# umodular_ctrl16.net
KiCad netlist of a schematic drawn in EAGLE
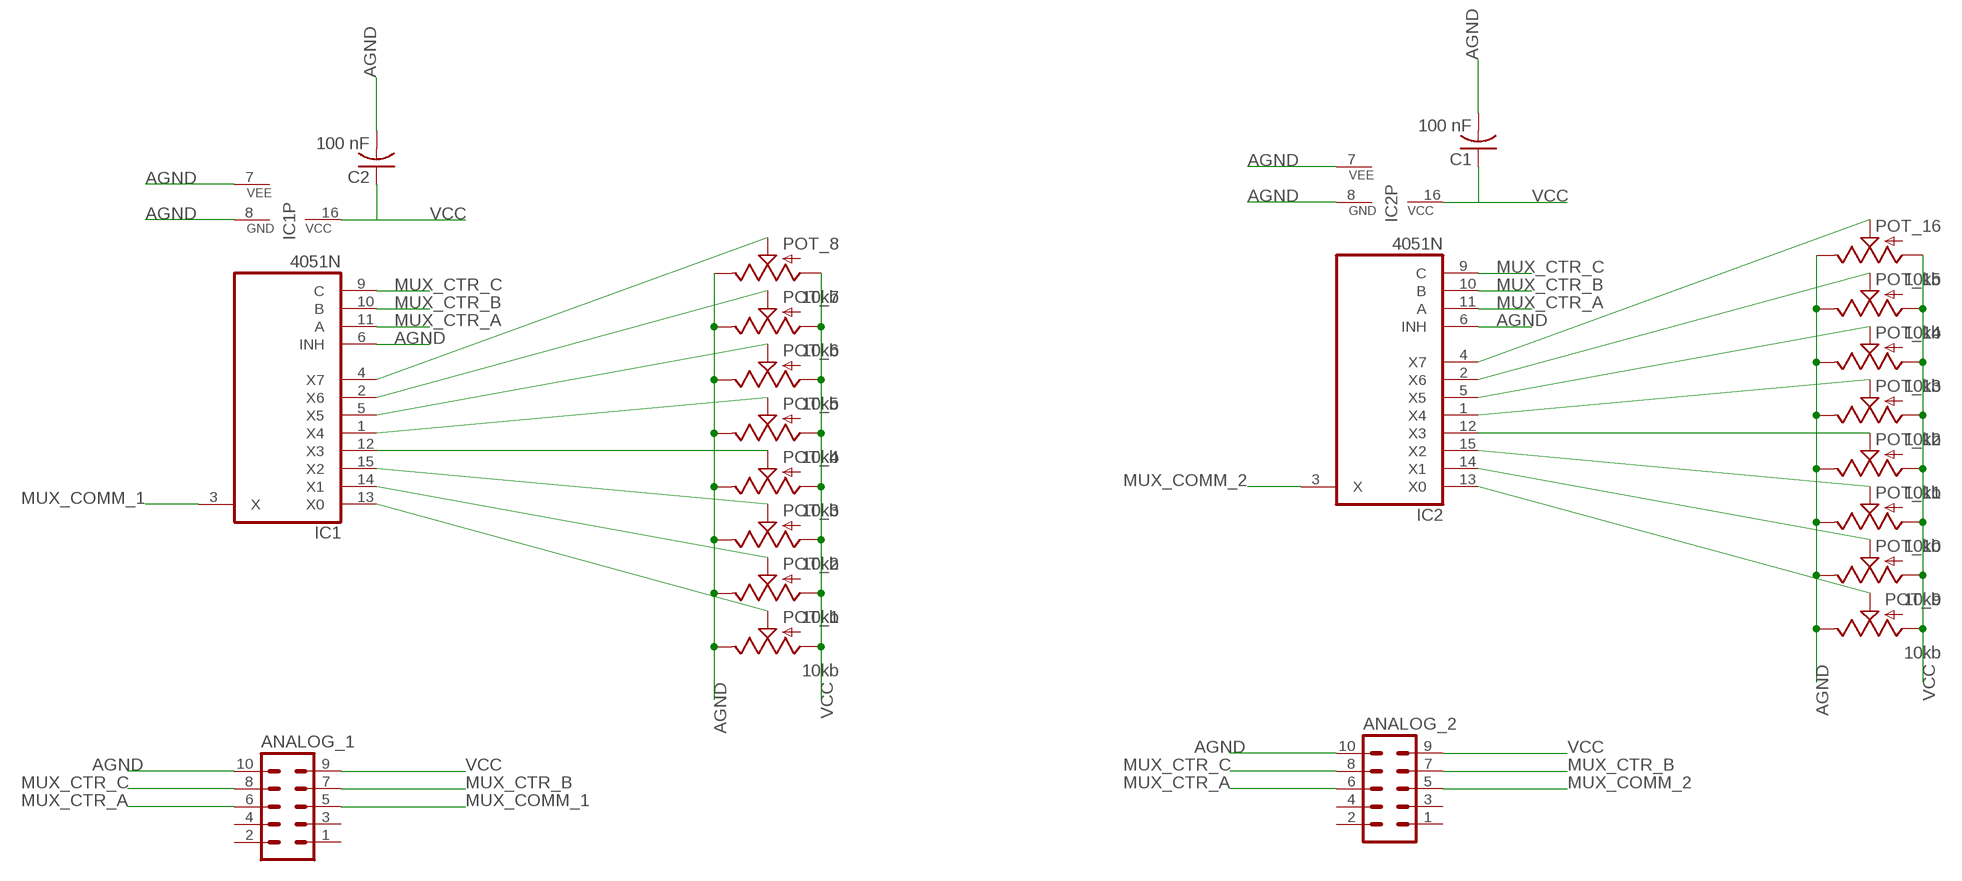
[diagram p0: schematic, sheet 1]
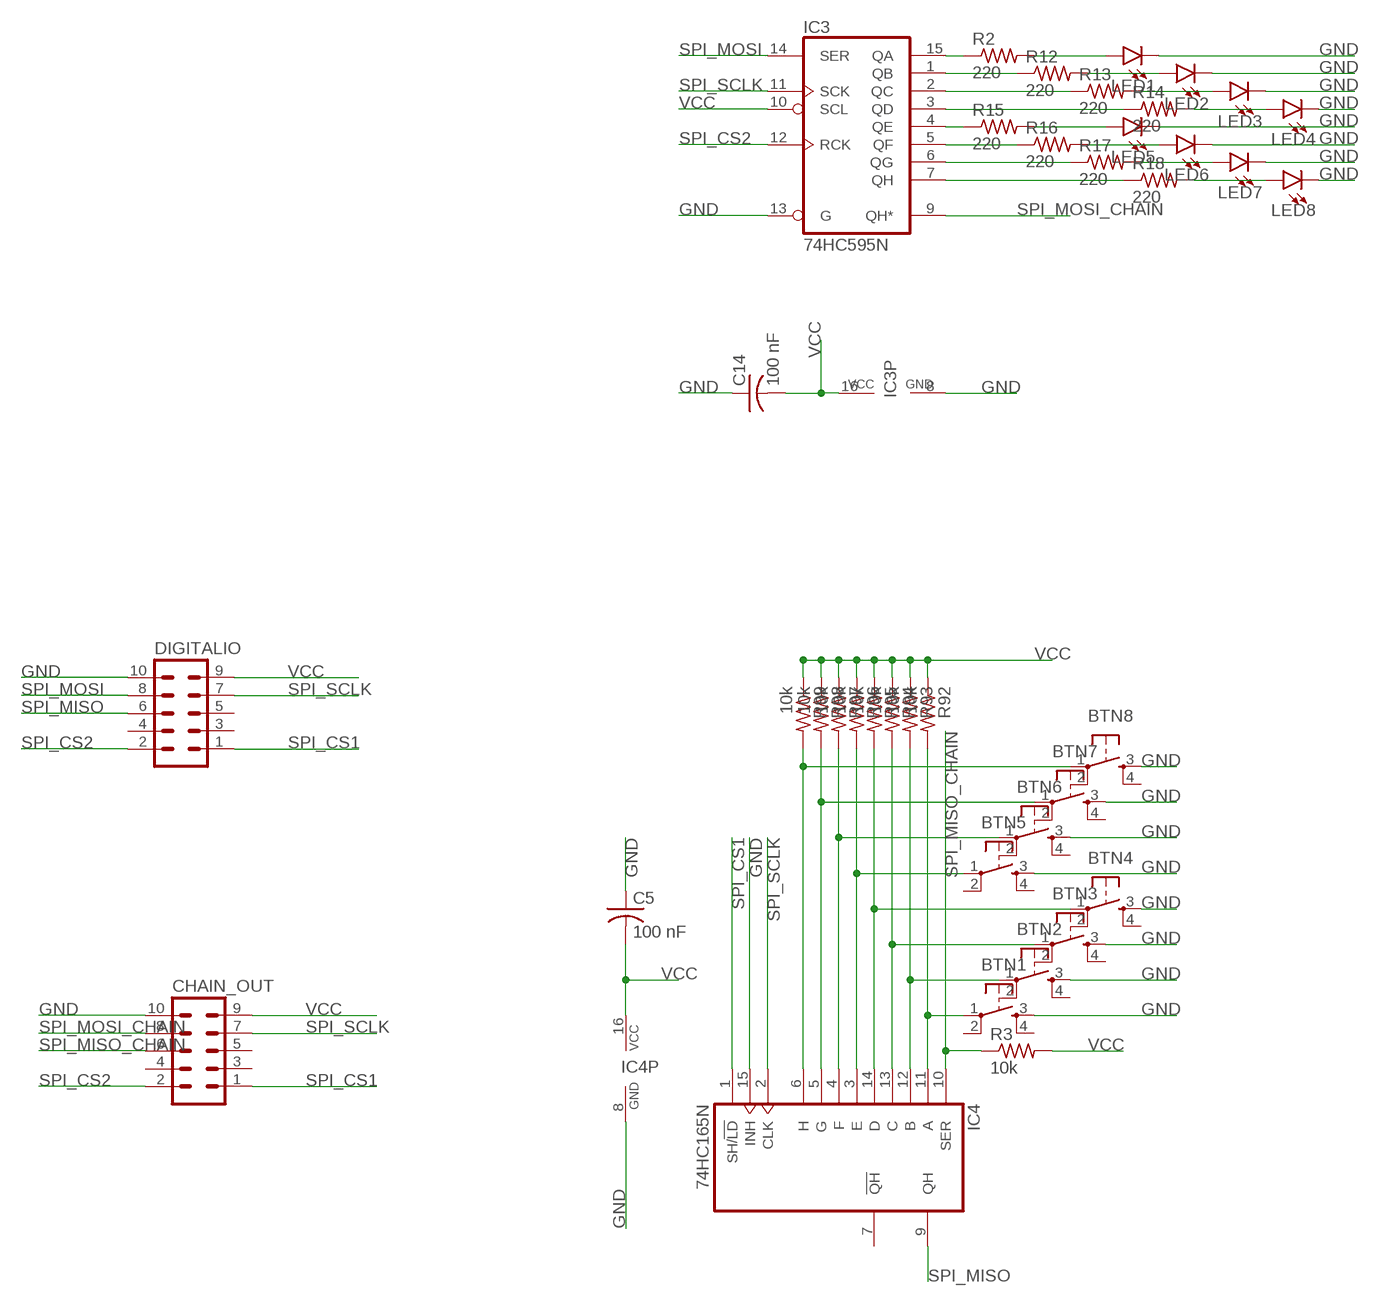
[diagram p1: schematic, sheet 2]

(export (version "E")
  (design (tool "Eeschema 10.0.6"))
  (components
    (comp (ref "ANALOG_1")
      (value "MA05-2")
      (footprint "eagle-import:MA05-2")
      (libsource (lib "eagle-import") (part "MA05-2"))
    )
    (comp (ref "ANALOG_2")
      (value "MA05-2")
      (footprint "eagle-import:MA05-2")
      (libsource (lib "eagle-import") (part "MA05-2"))
    )
    (comp (ref "C1")
      (value "100 nF")
      (footprint "eagle-import:C050-024X044")
      (libsource (lib "eagle-import") (part "C-US050-024X044"))
    )
    (comp (ref "C2")
      (value "100 nF")
      (footprint "eagle-import:C050-024X044")
      (libsource (lib "eagle-import") (part "C-US050-024X044"))
    )
    (comp (ref "IC1")
      (value "4051N")
      (footprint "eagle-import:DIL16")
      (libsource (lib "eagle-import") (part "4051N"))
    )
    (comp (ref "IC2")
      (value "4051N")
      (footprint "eagle-import:DIL16")
      (libsource (lib "eagle-import") (part "4051N"))
    )
    (comp (ref "POT_1")
      (value "10kb")
      (footprint "eagle-import:ALPS_POT")
      (libsource (lib "eagle-import") (part "POT"))
    )
    (comp (ref "POT_2")
      (value "10kb")
      (footprint "eagle-import:ALPS_POT")
      (libsource (lib "eagle-import") (part "POT"))
    )
    (comp (ref "POT_3")
      (value "10kb")
      (footprint "eagle-import:ALPS_POT")
      (libsource (lib "eagle-import") (part "POT"))
    )
    (comp (ref "POT_4")
      (value "10kb")
      (footprint "eagle-import:ALPS_POT")
      (libsource (lib "eagle-import") (part "POT"))
    )
    (comp (ref "POT_5")
      (value "10kb")
      (footprint "eagle-import:ALPS_POT")
      (libsource (lib "eagle-import") (part "POT"))
    )
    (comp (ref "POT_6")
      (value "10kb")
      (footprint "eagle-import:ALPS_POT")
      (libsource (lib "eagle-import") (part "POT"))
    )
    (comp (ref "POT_7")
      (value "10kb")
      (footprint "eagle-import:ALPS_POT")
      (libsource (lib "eagle-import") (part "POT"))
    )
    (comp (ref "POT_8")
      (value "10kb")
      (footprint "eagle-import:ALPS_POT")
      (libsource (lib "eagle-import") (part "POT"))
    )
    (comp (ref "POT_9")
      (value "10kb")
      (footprint "eagle-import:ALPS_POT")
      (libsource (lib "eagle-import") (part "POT"))
    )
    (comp (ref "POT_10")
      (value "10kb")
      (footprint "eagle-import:ALPS_POT")
      (libsource (lib "eagle-import") (part "POT"))
    )
    (comp (ref "POT_11")
      (value "10kb")
      (footprint "eagle-import:ALPS_POT")
      (libsource (lib "eagle-import") (part "POT"))
    )
    (comp (ref "POT_12")
      (value "10kb")
      (footprint "eagle-import:ALPS_POT")
      (libsource (lib "eagle-import") (part "POT"))
    )
    (comp (ref "POT_13")
      (value "10kb")
      (footprint "eagle-import:ALPS_POT")
      (libsource (lib "eagle-import") (part "POT"))
    )
    (comp (ref "POT_14")
      (value "10kb")
      (footprint "eagle-import:ALPS_POT")
      (libsource (lib "eagle-import") (part "POT"))
    )
    (comp (ref "POT_15")
      (value "10kb")
      (footprint "eagle-import:ALPS_POT")
      (libsource (lib "eagle-import") (part "POT"))
    )
    (comp (ref "POT_16")
      (value "10kb")
      (footprint "eagle-import:ALPS_POT")
      (libsource (lib "eagle-import") (part "POT"))
    )
    (comp (ref "BTN1")
      (value "TAC_SWITCHPTH")
      (footprint "eagle-import:TACTILE-PTH")
      (libsource (lib "eagle-import") (part "TAC_SWITCHPTH"))
    )
    (comp (ref "BTN2")
      (value "TAC_SWITCHPTH")
      (footprint "eagle-import:TACTILE-PTH")
      (libsource (lib "eagle-import") (part "TAC_SWITCHPTH"))
    )
    (comp (ref "BTN3")
      (value "TAC_SWITCHPTH")
      (footprint "eagle-import:TACTILE-PTH")
      (libsource (lib "eagle-import") (part "TAC_SWITCHPTH"))
    )
    (comp (ref "BTN4")
      (value "TAC_SWITCHPTH")
      (footprint "eagle-import:TACTILE-PTH")
      (libsource (lib "eagle-import") (part "TAC_SWITCHPTH"))
    )
    (comp (ref "BTN5")
      (value "TAC_SWITCHPTH")
      (footprint "eagle-import:TACTILE-PTH")
      (libsource (lib "eagle-import") (part "TAC_SWITCHPTH"))
    )
    (comp (ref "BTN6")
      (value "TAC_SWITCHPTH")
      (footprint "eagle-import:TACTILE-PTH")
      (libsource (lib "eagle-import") (part "TAC_SWITCHPTH"))
    )
    (comp (ref "BTN7")
      (value "TAC_SWITCHPTH")
      (footprint "eagle-import:TACTILE-PTH")
      (libsource (lib "eagle-import") (part "TAC_SWITCHPTH"))
    )
    (comp (ref "BTN8")
      (value "TAC_SWITCHPTH")
      (footprint "eagle-import:TACTILE-PTH")
      (libsource (lib "eagle-import") (part "TAC_SWITCHPTH"))
    )
    (comp (ref "C5")
      (value "100 nF")
      (footprint "eagle-import:C050-024X044")
      (libsource (lib "eagle-import") (part "C-US050-024X044"))
    )
    (comp (ref "C14")
      (value "100 nF")
      (footprint "eagle-import:C050-024X044")
      (libsource (lib "eagle-import") (part "C-US050-024X044"))
    )
    (comp (ref "CHAIN_OUT")
      (value "MA05-2")
      (footprint "eagle-import:MA05-2")
      (libsource (lib "eagle-import") (part "MA05-2"))
    )
    (comp (ref "DIGITALIO")
      (value "MA05-2")
      (footprint "eagle-import:MA05-2")
      (libsource (lib "eagle-import") (part "MA05-2"))
    )
    (comp (ref "IC3")
      (value "74HC595N")
      (footprint "eagle-import:DIL16")
      (libsource (lib "eagle-import") (part "74595NHC"))
    )
    (comp (ref "IC4")
      (value "74HC165N")
      (footprint "eagle-import:DIL16")
      (libsource (lib "eagle-import") (part "74165NHC"))
    )
    (comp (ref "LED1")
      (value "LED3MM")
      (footprint "eagle-import:LED_3MM")
      (libsource (lib "eagle-import") (part "LED3MM"))
    )
    (comp (ref "LED2")
      (value "LED3MM")
      (footprint "eagle-import:LED_3MM")
      (libsource (lib "eagle-import") (part "LED3MM"))
    )
    (comp (ref "LED3")
      (value "LED3MM")
      (footprint "eagle-import:LED_3MM")
      (libsource (lib "eagle-import") (part "LED3MM"))
    )
    (comp (ref "LED4")
      (value "LED3MM")
      (footprint "eagle-import:LED_3MM")
      (libsource (lib "eagle-import") (part "LED3MM"))
    )
    (comp (ref "LED5")
      (value "LED3MM")
      (footprint "eagle-import:LED_3MM")
      (libsource (lib "eagle-import") (part "LED3MM"))
    )
    (comp (ref "LED6")
      (value "LED3MM")
      (footprint "eagle-import:LED_3MM")
      (libsource (lib "eagle-import") (part "LED3MM"))
    )
    (comp (ref "LED7")
      (value "LED3MM")
      (footprint "eagle-import:LED_3MM")
      (libsource (lib "eagle-import") (part "LED3MM"))
    )
    (comp (ref "LED8")
      (value "LED3MM")
      (footprint "eagle-import:LED_3MM")
      (libsource (lib "eagle-import") (part "LED3MM"))
    )
    (comp (ref "R2")
      (value "220")
      (footprint "eagle-import:0204_7")
      (libsource (lib "eagle-import") (part "R-US_0204/7"))
    )
    (comp (ref "R3")
      (value "10k")
      (footprint "eagle-import:0204_7")
      (libsource (lib "eagle-import") (part "resistor_R-US_0204/7"))
    )
    (comp (ref "R12")
      (value "220")
      (footprint "eagle-import:0204_7")
      (libsource (lib "eagle-import") (part "R-US_0204/7"))
    )
    (comp (ref "R13")
      (value "220")
      (footprint "eagle-import:0204_7")
      (libsource (lib "eagle-import") (part "R-US_0204/7"))
    )
    (comp (ref "R14")
      (value "220")
      (footprint "eagle-import:0204_7")
      (libsource (lib "eagle-import") (part "R-US_0204/7"))
    )
    (comp (ref "R15")
      (value "220")
      (footprint "eagle-import:0204_7")
      (libsource (lib "eagle-import") (part "R-US_0204/7"))
    )
    (comp (ref "R16")
      (value "220")
      (footprint "eagle-import:0204_7")
      (libsource (lib "eagle-import") (part "R-US_0204/7"))
    )
    (comp (ref "R17")
      (value "220")
      (footprint "eagle-import:0204_7")
      (libsource (lib "eagle-import") (part "R-US_0204/7"))
    )
    (comp (ref "R18")
      (value "220")
      (footprint "eagle-import:0204_7")
      (libsource (lib "eagle-import") (part "R-US_0204/7"))
    )
    (comp (ref "R92")
      (value "10k")
      (footprint "eagle-import:0204_7")
      (libsource (lib "eagle-import") (part "resistor_R-US_0204/7"))
    )
    (comp (ref "R93")
      (value "10k")
      (footprint "eagle-import:0204_7")
      (libsource (lib "eagle-import") (part "resistor_R-US_0204/7"))
    )
    (comp (ref "R94")
      (value "10k")
      (footprint "eagle-import:0204_7")
      (libsource (lib "eagle-import") (part "resistor_R-US_0204/7"))
    )
    (comp (ref "R95")
      (value "10k")
      (footprint "eagle-import:0204_7")
      (libsource (lib "eagle-import") (part "resistor_R-US_0204/7"))
    )
    (comp (ref "R96")
      (value "10k")
      (footprint "eagle-import:0204_7")
      (libsource (lib "eagle-import") (part "resistor_R-US_0204/7"))
    )
    (comp (ref "R97")
      (value "10k")
      (footprint "eagle-import:0204_7")
      (libsource (lib "eagle-import") (part "resistor_R-US_0204/7"))
    )
    (comp (ref "R98")
      (value "10k")
      (footprint "eagle-import:0204_7")
      (libsource (lib "eagle-import") (part "resistor_R-US_0204/7"))
    )
    (comp (ref "R99")
      (value "10k")
      (footprint "eagle-import:0204_7")
      (libsource (lib "eagle-import") (part "resistor_R-US_0204/7"))
    )
  )
  (nets
    (net (code "1") (name "AGND") (class "Default")
      (node (ref "ANALOG_1") (pin "10") (pinfunction "10_10") (pintype "passive"))
      (node (ref "ANALOG_2") (pin "10") (pinfunction "10_10") (pintype "passive"))
      (node (ref "C1") (pin "2") (pinfunction "2_2") (pintype "passive"))
      (node (ref "C2") (pin "2") (pinfunction "2_2") (pintype "passive"))
      (node (ref "IC1") (pin "6") (pinfunction "INH_6") (pintype "input"))
      (node (ref "IC1") (pin "7") (pinfunction "VEE_7") (pintype "power_in"))
      (node (ref "IC1") (pin "8") (pinfunction "GND_8") (pintype "power_in"))
      (node (ref "IC2") (pin "6") (pinfunction "INH_6") (pintype "input"))
      (node (ref "IC2") (pin "7") (pinfunction "VEE_7") (pintype "power_in"))
      (node (ref "IC2") (pin "8") (pinfunction "GND_8") (pintype "power_in"))
      (node (ref "POT_1") (pin "P$1") (pinfunction "E_P$1") (pintype "passive"))
      (node (ref "POT_10") (pin "P$1") (pinfunction "E_P$1") (pintype "passive"))
      (node (ref "POT_11") (pin "P$1") (pinfunction "E_P$1") (pintype "passive"))
      (node (ref "POT_12") (pin "P$1") (pinfunction "E_P$1") (pintype "passive"))
      (node (ref "POT_13") (pin "P$1") (pinfunction "E_P$1") (pintype "passive"))
      (node (ref "POT_14") (pin "P$1") (pinfunction "E_P$1") (pintype "passive"))
      (node (ref "POT_15") (pin "P$1") (pinfunction "E_P$1") (pintype "passive"))
      (node (ref "POT_16") (pin "P$1") (pinfunction "E_P$1") (pintype "passive"))
      (node (ref "POT_2") (pin "P$1") (pinfunction "E_P$1") (pintype "passive"))
      (node (ref "POT_3") (pin "P$1") (pinfunction "E_P$1") (pintype "passive"))
      (node (ref "POT_4") (pin "P$1") (pinfunction "E_P$1") (pintype "passive"))
      (node (ref "POT_5") (pin "P$1") (pinfunction "E_P$1") (pintype "passive"))
      (node (ref "POT_6") (pin "P$1") (pinfunction "E_P$1") (pintype "passive"))
      (node (ref "POT_7") (pin "P$1") (pinfunction "E_P$1") (pintype "passive"))
      (node (ref "POT_8") (pin "P$1") (pinfunction "E_P$1") (pintype "passive"))
      (node (ref "POT_9") (pin "P$1") (pinfunction "E_P$1") (pintype "passive"))
    )
    (net (code "2") (name "GND") (class "Default")
      (node (ref "BTN1") (pin "3") (pinfunction "3_3") (pintype "passive"))
      (node (ref "BTN2") (pin "3") (pinfunction "3_3") (pintype "passive"))
      (node (ref "BTN3") (pin "3") (pinfunction "3_3") (pintype "passive"))
      (node (ref "BTN4") (pin "3") (pinfunction "3_3") (pintype "passive"))
      (node (ref "BTN5") (pin "3") (pinfunction "3_3") (pintype "passive"))
      (node (ref "BTN6") (pin "3") (pinfunction "3_3") (pintype "passive"))
      (node (ref "BTN7") (pin "3") (pinfunction "3_3") (pintype "passive"))
      (node (ref "BTN8") (pin "3") (pinfunction "3_3") (pintype "passive"))
      (node (ref "C14") (pin "1") (pinfunction "1_1") (pintype "passive"))
      (node (ref "C5") (pin "1") (pinfunction "1_1") (pintype "passive"))
      (node (ref "CHAIN_OUT") (pin "10") (pinfunction "10_10") (pintype "passive"))
      (node (ref "DIGITALIO") (pin "10") (pinfunction "10_10") (pintype "passive"))
      (node (ref "IC3") (pin "13") (pinfunction "G_13") (pintype "input"))
      (node (ref "IC3") (pin "8") (pinfunction "GND_8") (pintype "power_in"))
      (node (ref "IC4") (pin "15") (pinfunction "INH_15") (pintype "input"))
      (node (ref "IC4") (pin "8") (pinfunction "GND_8") (pintype "power_in"))
      (node (ref "LED1") (pin "K") (pinfunction "C_K") (pintype "passive"))
      (node (ref "LED2") (pin "K") (pinfunction "C_K") (pintype "passive"))
      (node (ref "LED3") (pin "K") (pinfunction "C_K") (pintype "passive"))
      (node (ref "LED4") (pin "K") (pinfunction "C_K") (pintype "passive"))
      (node (ref "LED5") (pin "K") (pinfunction "C_K") (pintype "passive"))
      (node (ref "LED6") (pin "K") (pinfunction "C_K") (pintype "passive"))
      (node (ref "LED7") (pin "K") (pinfunction "C_K") (pintype "passive"))
      (node (ref "LED8") (pin "K") (pinfunction "C_K") (pintype "passive"))
    )
    (net (code "3") (name "MUX_COMM_1") (class "Default")
      (node (ref "ANALOG_1") (pin "5") (pinfunction "5_5") (pintype "passive"))
      (node (ref "IC1") (pin "3") (pinfunction "X_3") (pintype "bidirectional"))
    )
    (net (code "4") (name "MUX_COMM_2") (class "Default")
      (node (ref "ANALOG_2") (pin "5") (pinfunction "5_5") (pintype "passive"))
      (node (ref "IC2") (pin "3") (pinfunction "X_3") (pintype "bidirectional"))
    )
    (net (code "5") (name "MUX_CTR_A") (class "Default")
      (node (ref "ANALOG_1") (pin "6") (pinfunction "6_6") (pintype "passive"))
      (node (ref "ANALOG_2") (pin "6") (pinfunction "6_6") (pintype "passive"))
      (node (ref "IC1") (pin "11") (pinfunction "A_11") (pintype "input"))
      (node (ref "IC2") (pin "11") (pinfunction "A_11") (pintype "input"))
    )
    (net (code "6") (name "MUX_CTR_B") (class "Default")
      (node (ref "ANALOG_1") (pin "7") (pinfunction "7_7") (pintype "passive"))
      (node (ref "ANALOG_2") (pin "7") (pinfunction "7_7") (pintype "passive"))
      (node (ref "IC1") (pin "10") (pinfunction "B_10") (pintype "input"))
      (node (ref "IC2") (pin "10") (pinfunction "B_10") (pintype "input"))
    )
    (net (code "7") (name "MUX_CTR_C") (class "Default")
      (node (ref "ANALOG_1") (pin "8") (pinfunction "8_8") (pintype "passive"))
      (node (ref "ANALOG_2") (pin "8") (pinfunction "8_8") (pintype "passive"))
      (node (ref "IC1") (pin "9") (pinfunction "C_9") (pintype "input"))
      (node (ref "IC2") (pin "9") (pinfunction "C_9") (pintype "input"))
    )
    (net (code "8") (name "Net-(IC1A-X0)") (class "Default")
      (node (ref "IC1") (pin "13") (pinfunction "X0_13") (pintype "bidirectional"))
      (node (ref "POT_1") (pin "P$2") (pinfunction "S_P$2") (pintype "passive"))
    )
    (net (code "9") (name "Net-(IC1A-X1)") (class "Default")
      (node (ref "IC1") (pin "14") (pinfunction "X1_14") (pintype "bidirectional"))
      (node (ref "POT_2") (pin "P$2") (pinfunction "S_P$2") (pintype "passive"))
    )
    (net (code "10") (name "Net-(IC1A-X2)") (class "Default")
      (node (ref "IC1") (pin "15") (pinfunction "X2_15") (pintype "bidirectional"))
      (node (ref "POT_3") (pin "P$2") (pinfunction "S_P$2") (pintype "passive"))
    )
    (net (code "11") (name "Net-(IC1A-X3)") (class "Default")
      (node (ref "IC1") (pin "12") (pinfunction "X3_12") (pintype "bidirectional"))
      (node (ref "POT_4") (pin "P$2") (pinfunction "S_P$2") (pintype "passive"))
    )
    (net (code "12") (name "Net-(IC1A-X4)") (class "Default")
      (node (ref "IC1") (pin "1") (pinfunction "X4_1") (pintype "bidirectional"))
      (node (ref "POT_5") (pin "P$2") (pinfunction "S_P$2") (pintype "passive"))
    )
    (net (code "13") (name "Net-(IC1A-X5)") (class "Default")
      (node (ref "IC1") (pin "5") (pinfunction "X5_5") (pintype "bidirectional"))
      (node (ref "POT_6") (pin "P$2") (pinfunction "S_P$2") (pintype "passive"))
    )
    (net (code "14") (name "Net-(IC1A-X6)") (class "Default")
      (node (ref "IC1") (pin "2") (pinfunction "X6_2") (pintype "bidirectional"))
      (node (ref "POT_7") (pin "P$2") (pinfunction "S_P$2") (pintype "passive"))
    )
    (net (code "15") (name "Net-(IC1A-X7)") (class "Default")
      (node (ref "IC1") (pin "4") (pinfunction "X7_4") (pintype "bidirectional"))
      (node (ref "POT_8") (pin "P$2") (pinfunction "S_P$2") (pintype "passive"))
    )
    (net (code "16") (name "Net-(IC2A-X0)") (class "Default")
      (node (ref "IC2") (pin "13") (pinfunction "X0_13") (pintype "bidirectional"))
      (node (ref "POT_9") (pin "P$2") (pinfunction "S_P$2") (pintype "passive"))
    )
    (net (code "17") (name "Net-(IC2A-X1)") (class "Default")
      (node (ref "IC2") (pin "14") (pinfunction "X1_14") (pintype "bidirectional"))
      (node (ref "POT_10") (pin "P$2") (pinfunction "S_P$2") (pintype "passive"))
    )
    (net (code "18") (name "Net-(IC2A-X2)") (class "Default")
      (node (ref "IC2") (pin "15") (pinfunction "X2_15") (pintype "bidirectional"))
      (node (ref "POT_11") (pin "P$2") (pinfunction "S_P$2") (pintype "passive"))
    )
    (net (code "19") (name "Net-(IC2A-X3)") (class "Default")
      (node (ref "IC2") (pin "12") (pinfunction "X3_12") (pintype "bidirectional"))
      (node (ref "POT_12") (pin "P$2") (pinfunction "S_P$2") (pintype "passive"))
    )
    (net (code "20") (name "Net-(IC2A-X4)") (class "Default")
      (node (ref "IC2") (pin "1") (pinfunction "X4_1") (pintype "bidirectional"))
      (node (ref "POT_13") (pin "P$2") (pinfunction "S_P$2") (pintype "passive"))
    )
    (net (code "21") (name "Net-(IC2A-X5)") (class "Default")
      (node (ref "IC2") (pin "5") (pinfunction "X5_5") (pintype "bidirectional"))
      (node (ref "POT_14") (pin "P$2") (pinfunction "S_P$2") (pintype "passive"))
    )
    (net (code "22") (name "Net-(IC2A-X6)") (class "Default")
      (node (ref "IC2") (pin "2") (pinfunction "X6_2") (pintype "bidirectional"))
      (node (ref "POT_15") (pin "P$2") (pinfunction "S_P$2") (pintype "passive"))
    )
    (net (code "23") (name "Net-(IC2A-X7)") (class "Default")
      (node (ref "IC2") (pin "4") (pinfunction "X7_4") (pintype "bidirectional"))
      (node (ref "POT_16") (pin "P$2") (pinfunction "S_P$2") (pintype "passive"))
    )
    (net (code "24") (name "Net-(IC3A-QA)") (class "Default")
      (node (ref "IC3") (pin "15") (pinfunction "QA_15") (pintype "tri_state"))
      (node (ref "R2") (pin "1") (pinfunction "1_1") (pintype "passive"))
    )
    (net (code "25") (name "Net-(IC3A-QB)") (class "Default")
      (node (ref "IC3") (pin "1") (pinfunction "QB_1") (pintype "tri_state"))
      (node (ref "R12") (pin "1") (pinfunction "1_1") (pintype "passive"))
    )
    (net (code "26") (name "Net-(IC3A-QC)") (class "Default")
      (node (ref "IC3") (pin "2") (pinfunction "QC_2") (pintype "tri_state"))
      (node (ref "R13") (pin "1") (pinfunction "1_1") (pintype "passive"))
    )
    (net (code "27") (name "Net-(IC3A-QD)") (class "Default")
      (node (ref "IC3") (pin "3") (pinfunction "QD_3") (pintype "tri_state"))
      (node (ref "R14") (pin "1") (pinfunction "1_1") (pintype "passive"))
    )
    (net (code "28") (name "Net-(IC3A-QE)") (class "Default")
      (node (ref "IC3") (pin "4") (pinfunction "QE_4") (pintype "tri_state"))
      (node (ref "R15") (pin "1") (pinfunction "1_1") (pintype "passive"))
    )
    (net (code "29") (name "Net-(IC3A-QF)") (class "Default")
      (node (ref "IC3") (pin "5") (pinfunction "QF_5") (pintype "tri_state"))
      (node (ref "R16") (pin "1") (pinfunction "1_1") (pintype "passive"))
    )
    (net (code "30") (name "Net-(IC3A-QG)") (class "Default")
      (node (ref "IC3") (pin "6") (pinfunction "QG_6") (pintype "tri_state"))
      (node (ref "R17") (pin "1") (pinfunction "1_1") (pintype "passive"))
    )
    (net (code "31") (name "Net-(IC3A-QH)") (class "Default")
      (node (ref "IC3") (pin "7") (pinfunction "QH_7") (pintype "tri_state"))
      (node (ref "R18") (pin "1") (pinfunction "1_1") (pintype "passive"))
    )
    (net (code "32") (name "Net-(IC4A-A)") (class "Default")
      (node (ref "BTN1") (pin "1") (pinfunction "1_1") (pintype "passive"))
      (node (ref "IC4") (pin "11") (pinfunction "A_11") (pintype "input"))
      (node (ref "R92") (pin "2") (pinfunction "2_2") (pintype "passive"))
    )
    (net (code "33") (name "Net-(IC4A-B)") (class "Default")
      (node (ref "BTN2") (pin "1") (pinfunction "1_1") (pintype "passive"))
      (node (ref "IC4") (pin "12") (pinfunction "B_12") (pintype "input"))
      (node (ref "R93") (pin "2") (pinfunction "2_2") (pintype "passive"))
    )
    (net (code "34") (name "Net-(IC4A-C)") (class "Default")
      (node (ref "BTN3") (pin "1") (pinfunction "1_1") (pintype "passive"))
      (node (ref "IC4") (pin "13") (pinfunction "C_13") (pintype "input"))
      (node (ref "R94") (pin "2") (pinfunction "2_2") (pintype "passive"))
    )
    (net (code "35") (name "Net-(IC4A-D)") (class "Default")
      (node (ref "BTN4") (pin "1") (pinfunction "1_1") (pintype "passive"))
      (node (ref "IC4") (pin "14") (pinfunction "D_14") (pintype "input"))
      (node (ref "R95") (pin "2") (pinfunction "2_2") (pintype "passive"))
    )
    (net (code "36") (name "Net-(IC4A-E)") (class "Default")
      (node (ref "BTN5") (pin "1") (pinfunction "1_1") (pintype "passive"))
      (node (ref "IC4") (pin "3") (pinfunction "E_3") (pintype "input"))
      (node (ref "R96") (pin "2") (pinfunction "2_2") (pintype "passive"))
    )
    (net (code "37") (name "Net-(IC4A-F)") (class "Default")
      (node (ref "BTN6") (pin "1") (pinfunction "1_1") (pintype "passive"))
      (node (ref "IC4") (pin "4") (pinfunction "F_4") (pintype "input"))
      (node (ref "R97") (pin "2") (pinfunction "2_2") (pintype "passive"))
    )
    (net (code "38") (name "Net-(IC4A-G)") (class "Default")
      (node (ref "BTN7") (pin "1") (pinfunction "1_1") (pintype "passive"))
      (node (ref "IC4") (pin "5") (pinfunction "G_5") (pintype "input"))
      (node (ref "R98") (pin "2") (pinfunction "2_2") (pintype "passive"))
    )
    (net (code "39") (name "Net-(IC4A-H)") (class "Default")
      (node (ref "BTN8") (pin "1") (pinfunction "1_1") (pintype "passive"))
      (node (ref "IC4") (pin "6") (pinfunction "H_6") (pintype "input"))
      (node (ref "R99") (pin "2") (pinfunction "2_2") (pintype "passive"))
    )
    (net (code "40") (name "Net-(LED1-PadA)") (class "Default")
      (node (ref "LED1") (pin "A") (pinfunction "A_A") (pintype "passive"))
      (node (ref "R2") (pin "2") (pinfunction "2_2") (pintype "passive"))
    )
    (net (code "41") (name "Net-(LED2-PadA)") (class "Default")
      (node (ref "LED2") (pin "A") (pinfunction "A_A") (pintype "passive"))
      (node (ref "R12") (pin "2") (pinfunction "2_2") (pintype "passive"))
    )
    (net (code "42") (name "Net-(LED3-PadA)") (class "Default")
      (node (ref "LED3") (pin "A") (pinfunction "A_A") (pintype "passive"))
      (node (ref "R13") (pin "2") (pinfunction "2_2") (pintype "passive"))
    )
    (net (code "43") (name "Net-(LED4-PadA)") (class "Default")
      (node (ref "LED4") (pin "A") (pinfunction "A_A") (pintype "passive"))
      (node (ref "R14") (pin "2") (pinfunction "2_2") (pintype "passive"))
    )
    (net (code "44") (name "Net-(LED5-PadA)") (class "Default")
      (node (ref "LED5") (pin "A") (pinfunction "A_A") (pintype "passive"))
      (node (ref "R15") (pin "2") (pinfunction "2_2") (pintype "passive"))
    )
    (net (code "45") (name "Net-(LED6-PadA)") (class "Default")
      (node (ref "LED6") (pin "A") (pinfunction "A_A") (pintype "passive"))
      (node (ref "R16") (pin "2") (pinfunction "2_2") (pintype "passive"))
    )
    (net (code "46") (name "Net-(LED7-PadA)") (class "Default")
      (node (ref "LED7") (pin "A") (pinfunction "A_A") (pintype "passive"))
      (node (ref "R17") (pin "2") (pinfunction "2_2") (pintype "passive"))
    )
    (net (code "47") (name "Net-(LED8-PadA)") (class "Default")
      (node (ref "LED8") (pin "A") (pinfunction "A_A") (pintype "passive"))
      (node (ref "R18") (pin "2") (pinfunction "2_2") (pintype "passive"))
    )
    (net (code "48") (name "SPI_CS1") (class "Default")
      (node (ref "CHAIN_OUT") (pin "1") (pinfunction "1_1") (pintype "passive"))
      (node (ref "DIGITALIO") (pin "1") (pinfunction "1_1") (pintype "passive"))
      (node (ref "IC4") (pin "1") (pinfunction "SH/~{LD}_1") (pintype "input"))
    )
    (net (code "49") (name "SPI_CS2") (class "Default")
      (node (ref "CHAIN_OUT") (pin "2") (pinfunction "2_2") (pintype "passive"))
      (node (ref "DIGITALIO") (pin "2") (pinfunction "2_2") (pintype "passive"))
      (node (ref "IC3") (pin "12") (pinfunction "RCK_12") (pintype "input"))
    )
    (net (code "50") (name "SPI_MISO") (class "Default")
      (node (ref "DIGITALIO") (pin "6") (pinfunction "6_6") (pintype "passive"))
      (node (ref "IC4") (pin "9") (pinfunction "QH_9") (pintype "output"))
    )
    (net (code "51") (name "SPI_MISO_CHAIN") (class "Default")
      (node (ref "CHAIN_OUT") (pin "6") (pinfunction "6_6") (pintype "passive"))
      (node (ref "IC4") (pin "10") (pinfunction "SER_10") (pintype "input"))
      (node (ref "R3") (pin "1") (pinfunction "1_1") (pintype "passive"))
    )
    (net (code "52") (name "SPI_MOSI") (class "Default")
      (node (ref "DIGITALIO") (pin "8") (pinfunction "8_8") (pintype "passive"))
      (node (ref "IC3") (pin "14") (pinfunction "SER_14") (pintype "input"))
    )
    (net (code "53") (name "SPI_MOSI_CHAIN") (class "Default")
      (node (ref "CHAIN_OUT") (pin "8") (pinfunction "8_8") (pintype "passive"))
      (node (ref "IC3") (pin "9") (pinfunction "QH*_9") (pintype "tri_state"))
    )
    (net (code "54") (name "SPI_SCLK") (class "Default")
      (node (ref "CHAIN_OUT") (pin "7") (pinfunction "7_7") (pintype "passive"))
      (node (ref "DIGITALIO") (pin "7") (pinfunction "7_7") (pintype "passive"))
      (node (ref "IC3") (pin "11") (pinfunction "SCK_11") (pintype "input"))
      (node (ref "IC4") (pin "2") (pinfunction "CLK_2") (pintype "input"))
    )
    (net (code "55") (name "VCC") (class "Default")
      (node (ref "ANALOG_1") (pin "9") (pinfunction "9_9") (pintype "passive"))
      (node (ref "ANALOG_2") (pin "9") (pinfunction "9_9") (pintype "passive"))
      (node (ref "C1") (pin "1") (pinfunction "1_1") (pintype "passive"))
      (node (ref "C14") (pin "2") (pinfunction "2_2") (pintype "passive"))
      (node (ref "C2") (pin "1") (pinfunction "1_1") (pintype "passive"))
      (node (ref "C5") (pin "2") (pinfunction "2_2") (pintype "passive"))
      (node (ref "CHAIN_OUT") (pin "9") (pinfunction "9_9") (pintype "passive"))
      (node (ref "DIGITALIO") (pin "9") (pinfunction "9_9") (pintype "passive"))
      (node (ref "IC1") (pin "16") (pinfunction "VCC_16") (pintype "power_in"))
      (node (ref "IC2") (pin "16") (pinfunction "VCC_16") (pintype "power_in"))
      (node (ref "IC3") (pin "10") (pinfunction "SCL_10") (pintype "input"))
      (node (ref "IC3") (pin "16") (pinfunction "VCC_16") (pintype "power_in"))
      (node (ref "IC4") (pin "16") (pinfunction "VCC_16") (pintype "power_in"))
      (node (ref "POT_1") (pin "P$3") (pinfunction "A_P$3") (pintype "passive"))
      (node (ref "POT_10") (pin "P$3") (pinfunction "A_P$3") (pintype "passive"))
      (node (ref "POT_11") (pin "P$3") (pinfunction "A_P$3") (pintype "passive"))
      (node (ref "POT_12") (pin "P$3") (pinfunction "A_P$3") (pintype "passive"))
      (node (ref "POT_13") (pin "P$3") (pinfunction "A_P$3") (pintype "passive"))
      (node (ref "POT_14") (pin "P$3") (pinfunction "A_P$3") (pintype "passive"))
      (node (ref "POT_15") (pin "P$3") (pinfunction "A_P$3") (pintype "passive"))
      (node (ref "POT_16") (pin "P$3") (pinfunction "A_P$3") (pintype "passive"))
      (node (ref "POT_2") (pin "P$3") (pinfunction "A_P$3") (pintype "passive"))
      (node (ref "POT_3") (pin "P$3") (pinfunction "A_P$3") (pintype "passive"))
      (node (ref "POT_4") (pin "P$3") (pinfunction "A_P$3") (pintype "passive"))
      (node (ref "POT_5") (pin "P$3") (pinfunction "A_P$3") (pintype "passive"))
      (node (ref "POT_6") (pin "P$3") (pinfunction "A_P$3") (pintype "passive"))
      (node (ref "POT_7") (pin "P$3") (pinfunction "A_P$3") (pintype "passive"))
      (node (ref "POT_8") (pin "P$3") (pinfunction "A_P$3") (pintype "passive"))
      (node (ref "POT_9") (pin "P$3") (pinfunction "A_P$3") (pintype "passive"))
      (node (ref "R3") (pin "2") (pinfunction "2_2") (pintype "passive"))
      (node (ref "R92") (pin "1") (pinfunction "1_1") (pintype "passive"))
      (node (ref "R93") (pin "1") (pinfunction "1_1") (pintype "passive"))
      (node (ref "R94") (pin "1") (pinfunction "1_1") (pintype "passive"))
      (node (ref "R95") (pin "1") (pinfunction "1_1") (pintype "passive"))
      (node (ref "R96") (pin "1") (pinfunction "1_1") (pintype "passive"))
      (node (ref "R97") (pin "1") (pinfunction "1_1") (pintype "passive"))
      (node (ref "R98") (pin "1") (pinfunction "1_1") (pintype "passive"))
      (node (ref "R99") (pin "1") (pinfunction "1_1") (pintype "passive"))
    )
    (net (code "56") (name "unconnected-(ANALOG_1-Pad1)") (class "Default")
      (node (ref "ANALOG_1") (pin "1") (pinfunction "1_1") (pintype "passive"))
    )
    (net (code "57") (name "unconnected-(ANALOG_1-Pad2)") (class "Default")
      (node (ref "ANALOG_1") (pin "2") (pinfunction "2_2") (pintype "passive"))
    )
    (net (code "58") (name "unconnected-(ANALOG_1-Pad3)") (class "Default")
      (node (ref "ANALOG_1") (pin "3") (pinfunction "3_3") (pintype "passive"))
    )
    (net (code "59") (name "unconnected-(ANALOG_1-Pad4)") (class "Default")
      (node (ref "ANALOG_1") (pin "4") (pinfunction "4_4") (pintype "passive"))
    )
    (net (code "60") (name "unconnected-(ANALOG_2-Pad1)") (class "Default")
      (node (ref "ANALOG_2") (pin "1") (pinfunction "1_1") (pintype "passive"))
    )
    (net (code "61") (name "unconnected-(ANALOG_2-Pad2)") (class "Default")
      (node (ref "ANALOG_2") (pin "2") (pinfunction "2_2") (pintype "passive"))
    )
    (net (code "62") (name "unconnected-(ANALOG_2-Pad3)") (class "Default")
      (node (ref "ANALOG_2") (pin "3") (pinfunction "3_3") (pintype "passive"))
    )
    (net (code "63") (name "unconnected-(ANALOG_2-Pad4)") (class "Default")
      (node (ref "ANALOG_2") (pin "4") (pinfunction "4_4") (pintype "passive"))
    )
    (net (code "64") (name "unconnected-(BTN1-Pad2)") (class "Default")
      (node (ref "BTN1") (pin "2") (pinfunction "2_2") (pintype "passive"))
    )
    (net (code "65") (name "unconnected-(BTN1-Pad4)") (class "Default")
      (node (ref "BTN1") (pin "4") (pinfunction "4_4") (pintype "passive"))
    )
    (net (code "66") (name "unconnected-(BTN2-Pad2)") (class "Default")
      (node (ref "BTN2") (pin "2") (pinfunction "2_2") (pintype "passive"))
    )
    (net (code "67") (name "unconnected-(BTN2-Pad4)") (class "Default")
      (node (ref "BTN2") (pin "4") (pinfunction "4_4") (pintype "passive"))
    )
    (net (code "68") (name "unconnected-(BTN3-Pad2)") (class "Default")
      (node (ref "BTN3") (pin "2") (pinfunction "2_2") (pintype "passive"))
    )
    (net (code "69") (name "unconnected-(BTN3-Pad4)") (class "Default")
      (node (ref "BTN3") (pin "4") (pinfunction "4_4") (pintype "passive"))
    )
    (net (code "70") (name "unconnected-(BTN4-Pad2)") (class "Default")
      (node (ref "BTN4") (pin "2") (pinfunction "2_2") (pintype "passive"))
    )
    (net (code "71") (name "unconnected-(BTN4-Pad4)") (class "Default")
      (node (ref "BTN4") (pin "4") (pinfunction "4_4") (pintype "passive"))
    )
    (net (code "72") (name "unconnected-(BTN5-Pad2)") (class "Default")
      (node (ref "BTN5") (pin "2") (pinfunction "2_2") (pintype "passive"))
    )
    (net (code "73") (name "unconnected-(BTN5-Pad4)") (class "Default")
      (node (ref "BTN5") (pin "4") (pinfunction "4_4") (pintype "passive"))
    )
    (net (code "74") (name "unconnected-(BTN6-Pad2)") (class "Default")
      (node (ref "BTN6") (pin "2") (pinfunction "2_2") (pintype "passive"))
    )
    (net (code "75") (name "unconnected-(BTN6-Pad4)") (class "Default")
      (node (ref "BTN6") (pin "4") (pinfunction "4_4") (pintype "passive"))
    )
    (net (code "76") (name "unconnected-(BTN7-Pad2)") (class "Default")
      (node (ref "BTN7") (pin "2") (pinfunction "2_2") (pintype "passive"))
    )
    (net (code "77") (name "unconnected-(BTN7-Pad4)") (class "Default")
      (node (ref "BTN7") (pin "4") (pinfunction "4_4") (pintype "passive"))
    )
    (net (code "78") (name "unconnected-(BTN8-Pad2)") (class "Default")
      (node (ref "BTN8") (pin "2") (pinfunction "2_2") (pintype "passive"))
    )
    (net (code "79") (name "unconnected-(BTN8-Pad4)") (class "Default")
      (node (ref "BTN8") (pin "4") (pinfunction "4_4") (pintype "passive"))
    )
    (net (code "80") (name "unconnected-(CHAIN_OUT-Pad3)") (class "Default")
      (node (ref "CHAIN_OUT") (pin "3") (pinfunction "3_3") (pintype "passive"))
    )
    (net (code "81") (name "unconnected-(CHAIN_OUT-Pad4)") (class "Default")
      (node (ref "CHAIN_OUT") (pin "4") (pinfunction "4_4") (pintype "passive"))
    )
    (net (code "82") (name "unconnected-(CHAIN_OUT-Pad5)") (class "Default")
      (node (ref "CHAIN_OUT") (pin "5") (pinfunction "5_5") (pintype "passive"))
    )
    (net (code "83") (name "unconnected-(DIGITALIO-Pad3)") (class "Default")
      (node (ref "DIGITALIO") (pin "3") (pinfunction "3_3") (pintype "passive"))
    )
    (net (code "84") (name "unconnected-(DIGITALIO-Pad4)") (class "Default")
      (node (ref "DIGITALIO") (pin "4") (pinfunction "4_4") (pintype "passive"))
    )
    (net (code "85") (name "unconnected-(DIGITALIO-Pad5)") (class "Default")
      (node (ref "DIGITALIO") (pin "5") (pinfunction "5_5") (pintype "passive"))
    )
    (net (code "86") (name "unconnected-(IC4A-~{QH}-Pad7)") (class "Default")
      (node (ref "IC4") (pin "7") (pinfunction "~{QH}_7") (pintype "output"))
    )
  )
)
